# Motor_control.net
KiCad netlist of a schematic drawn in Altium Designer
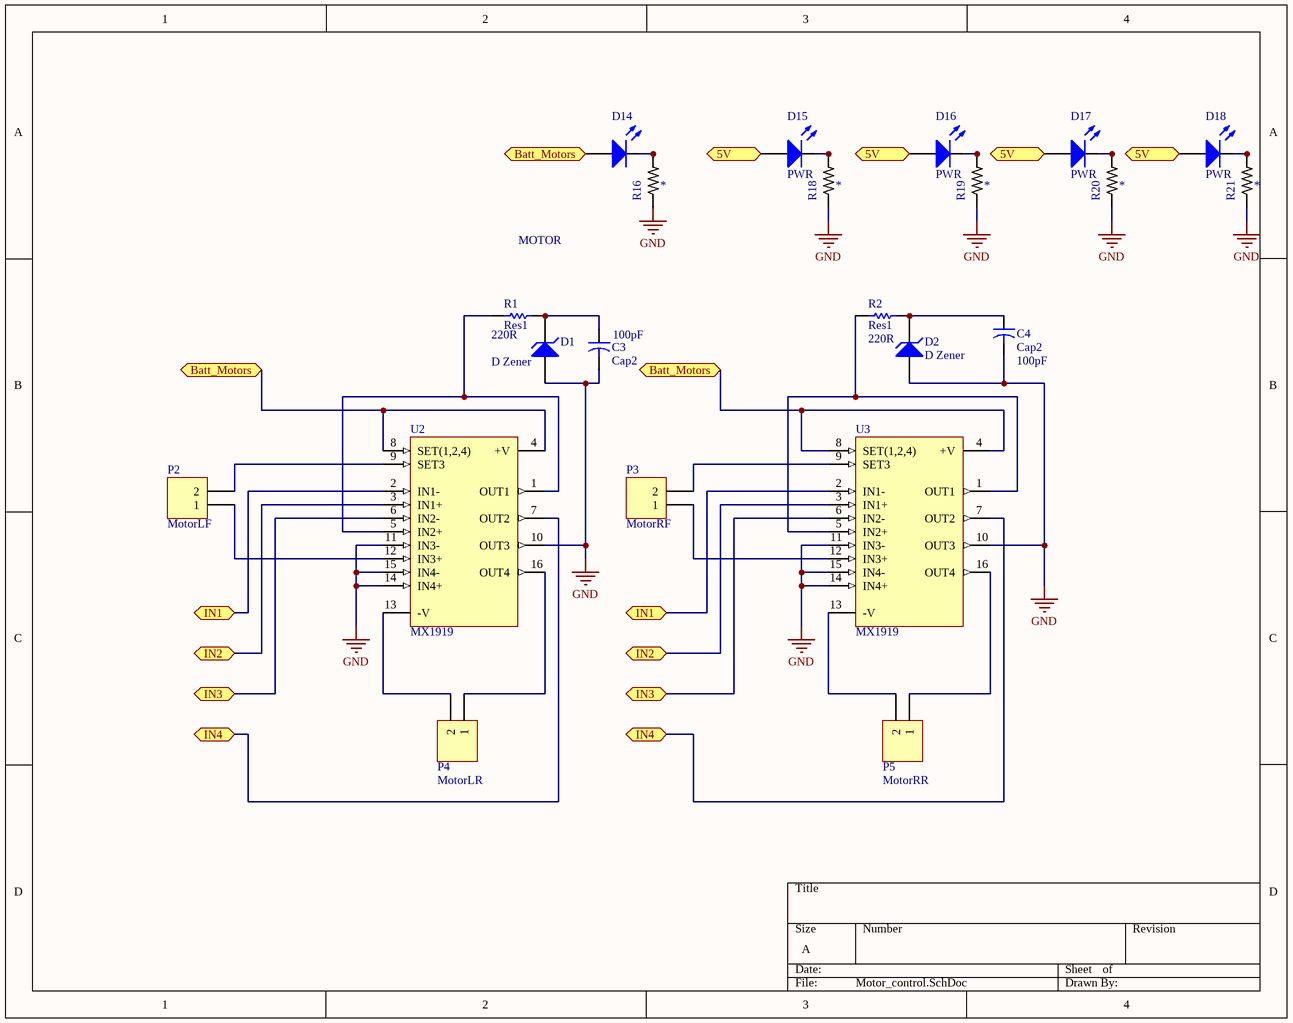
[diagram p0: Motor_control.SchDoc]

(export (version "E")
  (design (tool "Eeschema 10.0.6"))
  (components
    (comp (ref "C3")
      (value "Cap2")
      (footprint "CAPR5-4X5")
      (description "Capacitor")
      (fields (field (name "ALTIUM_VALUE") "100pF") (field (name "PUBLISHER") "Altium Limited"))
      (libsource (lib "Miscellaneous Devices") (part "Cap2"))
    )
    (comp (ref "C4")
      (value "Cap2")
      (footprint "CAPR5-4X5")
      (description "Capacitor")
      (fields (field (name "ALTIUM_VALUE") "100pF") (field (name "PUBLISHER") "Altium Limited"))
      (libsource (lib "Miscellaneous Devices") (part "Cap2"))
    )
    (comp (ref "D1")
      (value "D Zener")
      (footprint "DIODE-0.7")
      (description "Zener Diode")
      (fields (field (name "PUBLISHER") "Altium Limited"))
      (libsource (lib "Miscellaneous Devices") (part "D Zener"))
    )
    (comp (ref "D2")
      (value "D Zener")
      (footprint "DIODE-0.7")
      (description "Zener Diode")
      (fields (field (name "PUBLISHER") "Altium Limited"))
      (libsource (lib "Miscellaneous Devices") (part "D Zener"))
    )
    (comp (ref "D14")
      (value "MOTOR")
      (footprint "3.2X1.6X1.1")
      (description "Typical RED, GREEN, YELLOW, AMBER GaAs LED")
      (fields (field (name "PUBLISHER") "Altium Limited"))
      (libsource (lib "Miscellaneous Devices") (part "LED2"))
    )
    (comp (ref "D15")
      (value "PWR")
      (footprint "3.2X1.6X1.1")
      (description "Typical RED, GREEN, YELLOW, AMBER GaAs LED")
      (fields (field (name "PUBLISHER") "Altium Limited"))
      (libsource (lib "Miscellaneous Devices") (part "LED2"))
    )
    (comp (ref "D16")
      (value "PWR")
      (footprint "3.2X1.6X1.1")
      (description "Typical RED, GREEN, YELLOW, AMBER GaAs LED")
      (fields (field (name "PUBLISHER") "Altium Limited"))
      (libsource (lib "Miscellaneous Devices") (part "LED2"))
    )
    (comp (ref "D17")
      (value "PWR")
      (footprint "3.2X1.6X1.1")
      (description "Typical RED, GREEN, YELLOW, AMBER GaAs LED")
      (fields (field (name "PUBLISHER") "Altium Limited"))
      (libsource (lib "Miscellaneous Devices") (part "LED2"))
    )
    (comp (ref "D18")
      (value "PWR")
      (footprint "3.2X1.6X1.1")
      (description "Typical RED, GREEN, YELLOW, AMBER GaAs LED")
      (fields (field (name "PUBLISHER") "Altium Limited"))
      (libsource (lib "Miscellaneous Devices") (part "LED2"))
    )
    (comp (ref "P2")
      (value "MotorLF")
      (footprint "Micro_Metal_Motor")
      (description "Header, 2-Pin")
      (fields (field (name "PUBLISHER") "Altium Limited"))
      (libsource (lib "") (part "Header 2_1"))
    )
    (comp (ref "P3")
      (value "MotorRF")
      (footprint "Micro_Metal_Motor")
      (description "Header, 2-Pin")
      (fields (field (name "PUBLISHER") "Altium Limited"))
      (libsource (lib "") (part "Header 2_1"))
    )
    (comp (ref "P4")
      (value "MotorLR")
      (footprint "Micro_Metal_Motor")
      (description "Header, 2-Pin")
      (fields (field (name "PUBLISHER") "Altium Limited"))
      (libsource (lib "Miscellaneous Connectors") (part "Header 2"))
    )
    (comp (ref "P5")
      (value "MotorRR")
      (footprint "Micro_Metal_Motor")
      (description "Header, 2-Pin")
      (fields (field (name "PUBLISHER") "Altium Limited"))
      (libsource (lib "Miscellaneous Connectors") (part "Header 2"))
    )
    (comp (ref "R1")
      (value "Res1")
      (footprint "AXIAL-0.3")
      (description "Resistor")
      (fields (field (name "ALTIUM_VALUE") "220R") (field (name "PUBLISHER") "Altium Limited"))
      (libsource (lib "Miscellaneous Devices") (part "Res1"))
    )
    (comp (ref "R2")
      (value "Res1")
      (footprint "AXIAL-0.3")
      (description "Resistor")
      (fields (field (name "ALTIUM_VALUE") "220R") (field (name "PUBLISHER") "Altium Limited"))
      (libsource (lib "Miscellaneous Devices") (part "Res1"))
    )
    (comp (ref "R16")
      (value "Res_0805")
      (footprint "Res_0805")
      (description "Res Thick Film 0805 392 Ohm 1% 1/3W Â±100ppm/Â°C Molded SMD SMD T/R")
      (fields
        (field (name "MP") "CRGH0805F392R")
        (field (name "MF") "TE Connectivity")
        (field (name "ALTIUM_VALUE") "*")
      )
      (libsource (lib "IResc_lib") (part "Res_0805"))
    )
    (comp (ref "R18")
      (value "Res_0805")
      (footprint "Res_0805")
      (description "Res Thick Film 0805 392 Ohm 1% 1/3W Â±100ppm/Â°C Molded SMD SMD T/R")
      (fields
        (field (name "MP") "CRGH0805F392R")
        (field (name "MF") "TE Connectivity")
        (field (name "ALTIUM_VALUE") "*")
      )
      (libsource (lib "IResc_lib") (part "Res_0805"))
    )
    (comp (ref "R19")
      (value "Res_0805")
      (footprint "Res_0805")
      (description "Res Thick Film 0805 392 Ohm 1% 1/3W Â±100ppm/Â°C Molded SMD SMD T/R")
      (fields
        (field (name "MP") "CRGH0805F392R")
        (field (name "MF") "TE Connectivity")
        (field (name "ALTIUM_VALUE") "*")
      )
      (libsource (lib "IResc_lib") (part "Res_0805"))
    )
    (comp (ref "R20")
      (value "Res_0805")
      (footprint "Res_0805")
      (description "Res Thick Film 0805 392 Ohm 1% 1/3W Â±100ppm/Â°C Molded SMD SMD T/R")
      (fields
        (field (name "MP") "CRGH0805F392R")
        (field (name "MF") "TE Connectivity")
        (field (name "ALTIUM_VALUE") "*")
      )
      (libsource (lib "IResc_lib") (part "Res_0805"))
    )
    (comp (ref "R21")
      (value "Res_0805")
      (footprint "Res_0805")
      (description "Res Thick Film 0805 392 Ohm 1% 1/3W Â±100ppm/Â°C Molded SMD SMD T/R")
      (fields
        (field (name "MP") "CRGH0805F392R")
        (field (name "MF") "TE Connectivity")
        (field (name "ALTIUM_VALUE") "*")
      )
      (libsource (lib "IResc_lib") (part "Res_0805"))
    )
    (comp (ref "U2")
      (value "MX1919")
      (footprint "DIP16")
      (description "Programmable Quad Bipolar Operational Amplifier")
      (fields (field (name "PUBLISHER") "Altium Limited"))
      (libsource (lib "ST Operational Amplifier") (part "LM246N"))
    )
    (comp (ref "U3")
      (value "MX1919")
      (footprint "DIP16")
      (description "Programmable Quad Bipolar Operational Amplifier")
      (fields (field (name "PUBLISHER") "Altium Limited"))
      (libsource (lib "ST Operational Amplifier") (part "LM246N"))
    )
  )
  (nets
    (net (code "1") (name "/5V") (class "Default")
      (node (ref "D15") (pin "1") (pinfunction "A_1") (pintype "passive"))
      (node (ref "D16") (pin "1") (pinfunction "A_1") (pintype "passive"))
      (node (ref "D17") (pin "1") (pinfunction "A_1") (pintype "passive"))
      (node (ref "D18") (pin "1") (pinfunction "A_1") (pintype "passive"))
    )
    (net (code "2") (name "/Batt_Motors") (class "Default")
      (node (ref "D14") (pin "1") (pinfunction "A_1") (pintype "passive"))
      (node (ref "U2") (pin "4") (pinfunction "+V_4") (pintype "power_in"))
      (node (ref "U2") (pin "8") (pinfunction "SET(1,2,4)_8") (pintype "input"))
      (node (ref "U3") (pin "4") (pinfunction "+V_4") (pintype "power_in"))
      (node (ref "U3") (pin "8") (pinfunction "SET(1,2,4)_8") (pintype "input"))
    )
    (net (code "3") (name "/IN1") (class "Default")
      (node (ref "U2") (pin "2") (pinfunction "IN1-_2") (pintype "input"))
      (node (ref "U3") (pin "2") (pinfunction "IN1-_2") (pintype "input"))
    )
    (net (code "4") (name "/IN2") (class "Default")
      (node (ref "U2") (pin "3") (pinfunction "IN1+_3") (pintype "input"))
      (node (ref "U3") (pin "3") (pinfunction "IN1+_3") (pintype "input"))
    )
    (net (code "5") (name "/IN3") (class "Default")
      (node (ref "U2") (pin "6") (pinfunction "IN2-_6") (pintype "input"))
      (node (ref "U3") (pin "6") (pinfunction "IN2-_6") (pintype "input"))
    )
    (net (code "6") (name "/IN4") (class "Default")
      (node (ref "U2") (pin "7") (pinfunction "OUT2_7") (pintype "output"))
      (node (ref "U3") (pin "7") (pinfunction "OUT2_7") (pintype "output"))
    )
    (net (code "7") (name "GND") (class "Default")
      (node (ref "C3") (pin "2") (pinfunction "2_2") (pintype "passive"))
      (node (ref "C4") (pin "2") (pinfunction "2_2") (pintype "passive"))
      (node (ref "D1") (pin "1") (pinfunction "A_1") (pintype "passive"))
      (node (ref "D2") (pin "1") (pinfunction "A_1") (pintype "passive"))
      (node (ref "R16") (pin "1") (pinfunction "1_1") (pintype "passive"))
      (node (ref "R18") (pin "1") (pinfunction "1_1") (pintype "passive"))
      (node (ref "R19") (pin "1") (pinfunction "1_1") (pintype "passive"))
      (node (ref "R20") (pin "1") (pinfunction "1_1") (pintype "passive"))
      (node (ref "R21") (pin "1") (pinfunction "1_1") (pintype "passive"))
      (node (ref "U2") (pin "10") (pinfunction "OUT3_10") (pintype "output"))
      (node (ref "U2") (pin "11") (pinfunction "IN3-_11") (pintype "input"))
      (node (ref "U2") (pin "14") (pinfunction "IN4+_14") (pintype "input"))
      (node (ref "U2") (pin "15") (pinfunction "IN4-_15") (pintype "input"))
      (node (ref "U3") (pin "10") (pinfunction "OUT3_10") (pintype "output"))
      (node (ref "U3") (pin "11") (pinfunction "IN3-_11") (pintype "input"))
      (node (ref "U3") (pin "14") (pinfunction "IN4+_14") (pintype "input"))
      (node (ref "U3") (pin "15") (pinfunction "IN4-_15") (pintype "input"))
    )
    (net (code "8") (name "Net-(D1-K)") (class "Default")
      (node (ref "C3") (pin "1") (pinfunction "1_1") (pintype "passive"))
      (node (ref "D1") (pin "2") (pinfunction "K_2") (pintype "passive"))
      (node (ref "R1") (pin "1") (pinfunction "1_1") (pintype "passive"))
    )
    (net (code "9") (name "Net-(D2-K)") (class "Default")
      (node (ref "C4") (pin "1") (pinfunction "1_1") (pintype "passive"))
      (node (ref "D2") (pin "2") (pinfunction "K_2") (pintype "passive"))
      (node (ref "R2") (pin "1") (pinfunction "1_1") (pintype "passive"))
    )
    (net (code "10") (name "Net-(D14-K)") (class "Default")
      (node (ref "D14") (pin "2") (pinfunction "K_2") (pintype "passive"))
      (node (ref "R16") (pin "2") (pinfunction "2_2") (pintype "passive"))
    )
    (net (code "11") (name "Net-(D15-K)") (class "Default")
      (node (ref "D15") (pin "2") (pinfunction "K_2") (pintype "passive"))
      (node (ref "R18") (pin "2") (pinfunction "2_2") (pintype "passive"))
    )
    (net (code "12") (name "Net-(D16-K)") (class "Default")
      (node (ref "D16") (pin "2") (pinfunction "K_2") (pintype "passive"))
      (node (ref "R19") (pin "2") (pinfunction "2_2") (pintype "passive"))
    )
    (net (code "13") (name "Net-(D17-K)") (class "Default")
      (node (ref "D17") (pin "2") (pinfunction "K_2") (pintype "passive"))
      (node (ref "R20") (pin "2") (pinfunction "2_2") (pintype "passive"))
    )
    (net (code "14") (name "Net-(D18-K)") (class "Default")
      (node (ref "D18") (pin "2") (pinfunction "K_2") (pintype "passive"))
      (node (ref "R21") (pin "2") (pinfunction "2_2") (pintype "passive"))
    )
    (net (code "15") (name "Net-(U2--V)") (class "Default")
      (node (ref "P4") (pin "2") (pinfunction "2_2") (pintype "passive"))
      (node (ref "U2") (pin "13") (pinfunction "-V_13") (pintype "power_in"))
    )
    (net (code "16") (name "Net-(U2-IN2+)") (class "Default")
      (node (ref "R1") (pin "2") (pinfunction "2_2") (pintype "passive"))
      (node (ref "U2") (pin "1") (pinfunction "OUT1_1") (pintype "output"))
      (node (ref "U2") (pin "5") (pinfunction "IN2+_5") (pintype "input"))
    )
    (net (code "17") (name "Net-(U2-IN3+)") (class "Default")
      (node (ref "P2") (pin "1") (pinfunction "1_1") (pintype "passive"))
      (node (ref "U2") (pin "12") (pinfunction "IN3+_12") (pintype "input"))
    )
    (net (code "18") (name "Net-(U2-OUT4)") (class "Default")
      (node (ref "P4") (pin "1") (pinfunction "1_1") (pintype "passive"))
      (node (ref "U2") (pin "16") (pinfunction "OUT4_16") (pintype "output"))
    )
    (net (code "19") (name "Net-(U2-SET3)") (class "Default")
      (node (ref "P2") (pin "2") (pinfunction "2_2") (pintype "passive"))
      (node (ref "U2") (pin "9") (pinfunction "SET3_9") (pintype "input"))
    )
    (net (code "20") (name "Net-(U3--V)") (class "Default")
      (node (ref "P5") (pin "2") (pinfunction "2_2") (pintype "passive"))
      (node (ref "U3") (pin "13") (pinfunction "-V_13") (pintype "power_in"))
    )
    (net (code "21") (name "Net-(U3-IN2+)") (class "Default")
      (node (ref "R2") (pin "2") (pinfunction "2_2") (pintype "passive"))
      (node (ref "U3") (pin "1") (pinfunction "OUT1_1") (pintype "output"))
      (node (ref "U3") (pin "5") (pinfunction "IN2+_5") (pintype "input"))
    )
    (net (code "22") (name "Net-(U3-IN3+)") (class "Default")
      (node (ref "P3") (pin "1") (pinfunction "1_1") (pintype "passive"))
      (node (ref "U3") (pin "12") (pinfunction "IN3+_12") (pintype "input"))
    )
    (net (code "23") (name "Net-(U3-OUT4)") (class "Default")
      (node (ref "P5") (pin "1") (pinfunction "1_1") (pintype "passive"))
      (node (ref "U3") (pin "16") (pinfunction "OUT4_16") (pintype "output"))
    )
    (net (code "24") (name "Net-(U3-SET3)") (class "Default")
      (node (ref "P3") (pin "2") (pinfunction "2_2") (pintype "passive"))
      (node (ref "U3") (pin "9") (pinfunction "SET3_9") (pintype "input"))
    )
  )
)
